# 24V-5A-buck.net
KiCad netlist of a schematic drawn in Altium Designer
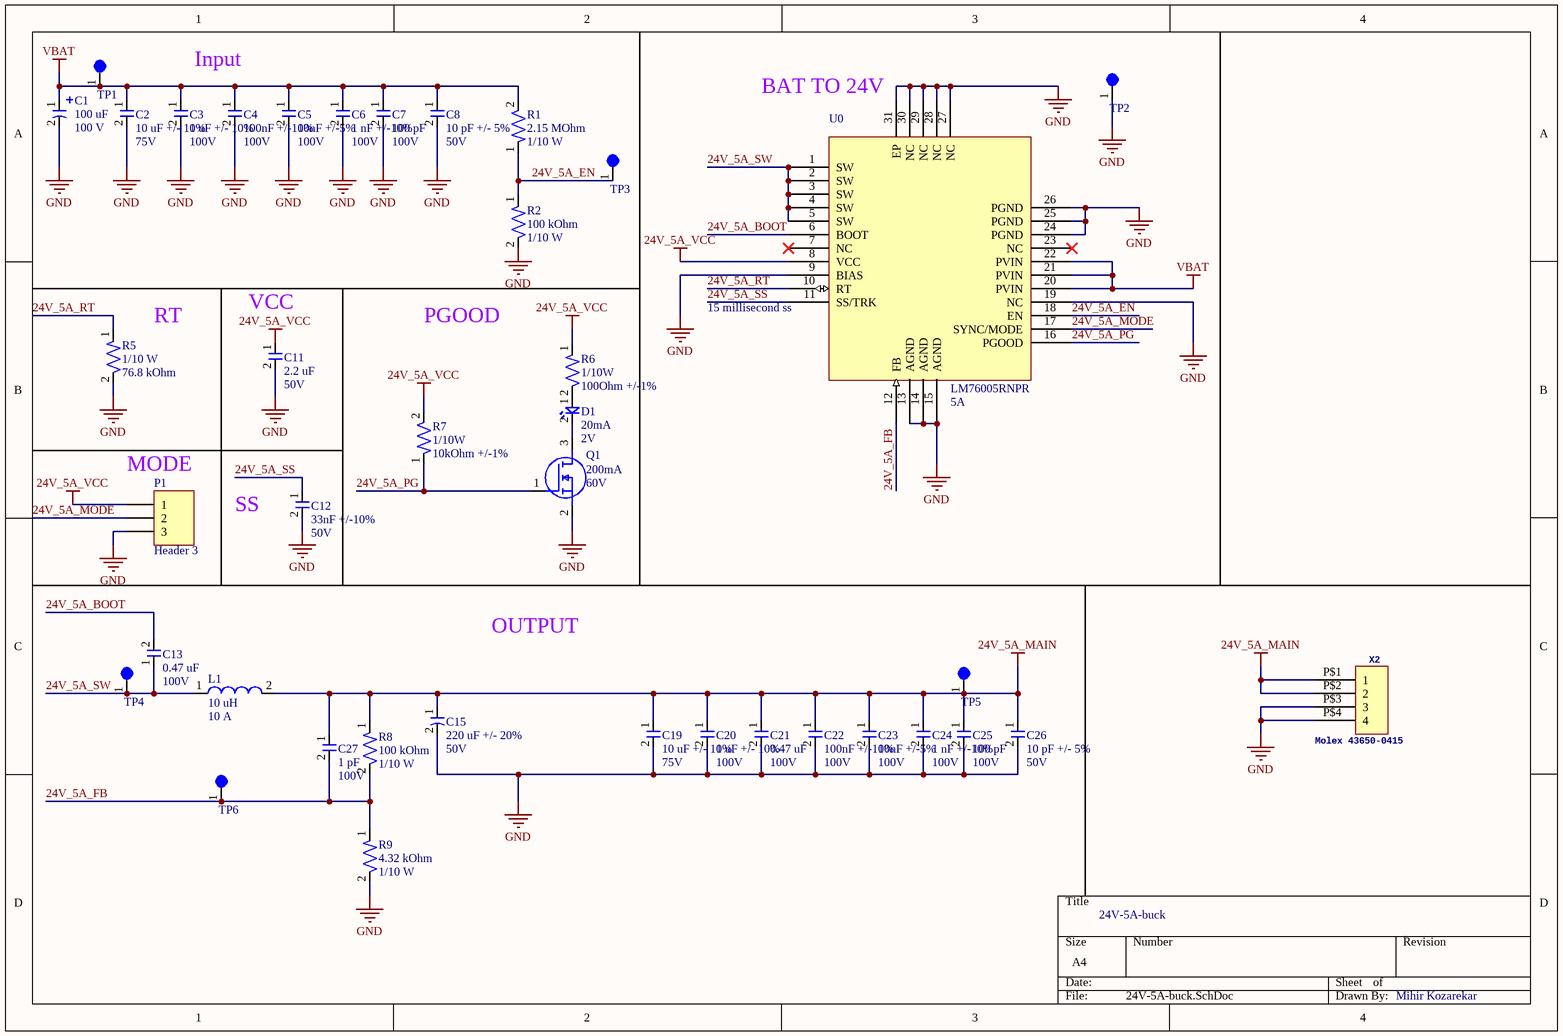
[diagram p0: 24V-5A-buck.SchDoc]

(export (version "E")
  (design (tool "Eeschema 10.0.6"))
  (components
    (comp (ref "C1")
      (value "100SEV100M12.5X16")
      (footprint "ELEC-100U-0001")
      (description "100 µF 100 V Aluminum Electrolytic Capacitors Radial, Can - SMD 2000 Hrs @ 85°C")
      (fields
        (field (name "MANUFACTURER") "Rubycon")
        (field (name "TOLERANCE") "+/- 20%")
        (field (name "CAPACITANCE") "100 uF")
        (field (name "VOLTAGE") "100 V")
      )
      (libsource (lib "MasterLib") (part "ELEC-100U-0001"))
    )
    (comp (ref "C2")
      (value "C3225X7R1N106K250AC")
      (footprint "CAP-1210")
      (description "10 µF ±10% 75V Ceramic Capacitor X7R 1210 (3225 Metric)")
      (fields (field (name "CAPACITANCE") "10 uF +/- 10%") (field (name "VOLTAGE RATING") "75V"))
      (libsource (lib "MasterLib") (part "CAP-10U-0004"))
    )
    (comp (ref "C3")
      (value "CL31B105KCHNNNE")
      (footprint "CAP-1206 - duplicate")
      (description "1 µF ±10% 100V Ceramic Capacitor X7R 1206 (3216 Metric)")
      (fields (field (name "CAPACITANCE") "1 uF +/- 10%") (field (name "VOLTAGE") "100V"))
      (libsource (lib "MasterLib") (part "CAP-1U-0001"))
    )
    (comp (ref "C4")
      (value "CC0603KRX7R0BB104")
      (footprint "CAP-0603")
      (description "CAP CER 0.1UF 100V X7R 0603")
      (fields
        (field (name "MANUFACTURER") "YAGEO")
        (field (name "CAPACITANCE") "100nF +/-10%")
        (field (name "VOLTAGE RATING") "100V")
      )
      (libsource (lib "MasterLib") (part "CAP-100N-0001"))
    )
    (comp (ref "C5")
      (value "C1608C0G2A103J080AC")
      (footprint "CAP-0603")
      (description "CAP CER 10000PF 100V C0G 0603")
      (fields
        (field (name "MANUFACTURER") "TDK Corporation")
        (field (name "CAPACITANCE") "10nF +/-5%")
        (field (name "VOLTAGE RATING") "100V")
      )
      (libsource (lib "MasterLib") (part "CAP-10N-0002"))
    )
    (comp (ref "C6")
      (value "C0603Y102K1RAC7867")
      (footprint "CAP-0603")
      (description "1000 pF ±10% 100V Ceramic Capacitor X7R 0603 (1608 Metric)")
      (fields (field (name "CAPACITANCE") "1 nF +/-10%") (field (name "VOLTAGE") "100V"))
      (libsource (lib "MasterLib") (part "CAP-1N-0001"))
    )
    (comp (ref "C7")
      (value "0603N101J101CT")
      (footprint "CAP-0603")
      (description "100 pF ±5% 100V Ceramic Capacitor C0G, NP0 0603 (1608 Metric)")
      (fields
        (field (name "TOLERANCE") "+/-5%")
        (field (name "CAPACITANCE") "100 pF")
        (field (name "VOLTAGE") "100V")
      )
      (libsource (lib "MasterLib") (part "CAP-100P-0002"))
    )
    (comp (ref "C8")
      (value "0603N100J500CT")
      (footprint "CAP-0603")
      (description "10 pF ±5% 50V Ceramic Capacitor C0G, NP0 0603 (1608 Metric)")
      (fields
        (field (name "MANUFACTURER") "Walshin Technology Corporation")
        (field (name "CAPACITANCE") "10 pF +/- 5%")
        (field (name "VOLTAGE RATING") "50V")
      )
      (libsource (lib "MasterLib") (part "CAP-10P-0001"))
    )
    (comp (ref "C11")
      (value "UMK107BBJ225KA-T")
      (footprint "CAP-0603")
      (description "2.2 µF ±10% 50V Ceramic Capacitor X5R 0603 (1608 Metric)")
      (fields (field (name "CAPACITANCE") "2.2 uF") (field (name "OLTAGE") "50V"))
      (libsource (lib "MasterLib") (part "CAP-2.2U-0001"))
    )
    (comp (ref "C12")
      (value "CC0603KRX7R9BB333")
      (footprint "CAP-0603")
      (description "0.033 µF ±10% 50V Ceramic Capacitor X7R 0603 (1608 Metric)")
      (fields
        (field (name "MANUFACTURER") "YAGEO")
        (field (name "CAPACITANCE") "33nF +/-10%")
        (field (name "VOLTAGE RATING") "50V")
      )
      (libsource (lib "MasterLib") (part "CAP-33N-0001"))
    )
    (comp (ref "C13")
      (value "KAM21KR72A474KL")
      (footprint "CAP-0805")
      (description "0.47 µF ±10% 100V Ceramic Capacitor X7R 0805 (2012 Metric)")
      (fields
        (field (name "TOLERANCE") "+/- 10%")
        (field (name "CAPACITANCE") "0.47 uF")
        (field (name "VOLTAGE") "100V")
      )
      (libsource (lib "MasterLib") (part "CAP-0.47U-0001"))
    )
    (comp (ref "C15")
      (value "50TZV220M10X10.5")
      (footprint "ELEC-220U-0003")
      (description "220 µF 50 V Aluminum Electrolytic Capacitors Radial, Can - SMD 2000 Hrs @ 105°C")
      (fields (field (name "CAPACITANCE") "220 uF +/- 20%") (field (name "VOLTAGE RATING") "50V"))
      (libsource (lib "MasterLib") (part "ELEC-220U-0003"))
    )
    (comp (ref "C19")
      (value "C3225X7R1N106K250AC")
      (footprint "CAP-1210")
      (description "10 µF ±10% 75V Ceramic Capacitor X7R 1210 (3225 Metric)")
      (fields (field (name "CAPACITANCE") "10 uF +/- 10%") (field (name "VOLTAGE RATING") "75V"))
      (libsource (lib "MasterLib") (part "CAP-10U-0004"))
    )
    (comp (ref "C20")
      (value "CL31B105KCHNNNE")
      (footprint "CAP-1206 - duplicate")
      (description "1 µF ±10% 100V Ceramic Capacitor X7R 1206 (3216 Metric)")
      (fields (field (name "CAPACITANCE") "1 uF +/- 10%") (field (name "VOLTAGE") "100V"))
      (libsource (lib "MasterLib") (part "CAP-1U-0001"))
    )
    (comp (ref "C21")
      (value "KAM21KR72A474KL")
      (footprint "CAP-0805")
      (description "0.47 µF ±10% 100V Ceramic Capacitor X7R 0805 (2012 Metric)")
      (fields
        (field (name "TOLERANCE") "+/- 10%")
        (field (name "CAPACITANCE") "0.47 uF")
        (field (name "VOLTAGE") "100V")
      )
      (libsource (lib "MasterLib") (part "CAP-0.47U-0001"))
    )
    (comp (ref "C22")
      (value "CC0603KRX7R0BB104")
      (footprint "CAP-0603")
      (description "CAP CER 0.1UF 100V X7R 0603")
      (fields
        (field (name "MANUFACTURER") "YAGEO")
        (field (name "CAPACITANCE") "100nF +/-10%")
        (field (name "VOLTAGE RATING") "100V")
      )
      (libsource (lib "MasterLib") (part "CAP-100N-0001"))
    )
    (comp (ref "C23")
      (value "C1608C0G2A103J080AC")
      (footprint "CAP-0603")
      (description "CAP CER 10000PF 100V C0G 0603")
      (fields
        (field (name "MANUFACTURER") "TDK Corporation")
        (field (name "CAPACITANCE") "10nF +/-5%")
        (field (name "VOLTAGE RATING") "100V")
      )
      (libsource (lib "MasterLib") (part "CAP-10N-0002"))
    )
    (comp (ref "C24")
      (value "C0603Y102K1RAC7867")
      (footprint "CAP-0603")
      (description "1000 pF ±10% 100V Ceramic Capacitor X7R 0603 (1608 Metric)")
      (fields (field (name "CAPACITANCE") "1 nF +/-10%") (field (name "VOLTAGE") "100V"))
      (libsource (lib "MasterLib") (part "CAP-1N-0001"))
    )
    (comp (ref "C25")
      (value "0603N101J101CT")
      (footprint "CAP-0603")
      (description "100 pF ±5% 100V Ceramic Capacitor C0G, NP0 0603 (1608 Metric)")
      (fields
        (field (name "TOLERANCE") "+/-5%")
        (field (name "CAPACITANCE") "100 pF")
        (field (name "VOLTAGE") "100V")
      )
      (libsource (lib "MasterLib") (part "CAP-100P-0002"))
    )
    (comp (ref "C26")
      (value "0603N100J500CT")
      (footprint "CAP-0603")
      (description "10 pF ±5% 50V Ceramic Capacitor C0G, NP0 0603 (1608 Metric)")
      (fields
        (field (name "MANUFACTURER") "Walshin Technology Corporation")
        (field (name "CAPACITANCE") "10 pF +/- 5%")
        (field (name "VOLTAGE RATING") "50V")
      )
      (libsource (lib "MasterLib") (part "CAP-10P-0001"))
    )
    (comp (ref "C27")
      (value "885012006087")
      (footprint "CAP-0603")
      (description "1 pF ±0.25pF 100V Ceramic Capacitor C0G, NP0 0603 (1608 Metric)")
      (fields
        (field (name "TOLERANCE") "+/- 0.25 pF")
        (field (name "CAPACITANCE") "1 pF")
        (field (name "VOLTAGE") "100V")
      )
      (libsource (lib "MasterLib") (part "CAP-1P-0001"))
    )
    (comp (ref "D1")
      (value "150060AS75000")
      (footprint "LED-0603")
      (description "CAP CER 0.1UF 100V X7R 0603")
      (fields
        (field (name "MANUFACTURER") "Wurth Electronik")
        (field (name "CURRENT RATING") "20mA")
        (field (name "VF") "2V")
      )
      (libsource (lib "MasterLib") (part "LED_Amber_0001"))
    )
    (comp (ref "L1")
      (value "SRP1270-100M")
      (footprint "PWRIND-10U-0002")
      (description "10 µH Shielded Drum Core, Wirewound Inductor 10 A 16.8mOhm Max Nonstandard")
      (fields
        (field (name "TOLERANCE") "+/- 20%")
        (field (name "INDUCTANCE") "10 uH")
        (field (name "DCI") "10 A")
      )
      (libsource (lib "MasterLib") (part "PWRIND-10U-0002"))
    )
    (comp (ref "P1")
      (value "Header 3")
      (footprint "HDR1X3")
      (description "Header, 3-Pin")
      (fields (field (name "PUBLISHER") "Altium Limited"))
      (libsource (lib "Miscellaneous Connectors") (part "Header 3"))
    )
    (comp (ref "Q1")
      (value "T2N7002AK,LM")
      (footprint "NMOS-SOT23-3")
      (description "MOSFET N-CH 60V 200MA SOT23")
      (fields
        (field (name "MANUFACTURER") "Toshiba")
        (field (name "ID-CONTINUOUS") "200mA")
        (field (name "VDS-MAX") "60V")
      )
      (libsource (lib "MasterLib") (part "NMOS-200MA-0001"))
    )
    (comp (ref "R1")
      (value "RC0603FR-072M15L")
      (footprint "RES-0603")
      (description "2.15 MOhms ±1% 0.1W, 1/10W Chip Resistor 0603 (1608 Metric) Moisture Resistant Thick Film")
      (fields
        (field (name "TOLERANCE") "+/-1%")
        (field (name "RESISTANCE") "2.15 MOhm")
        (field (name "POWER") "1/10 W")
      )
      (libsource (lib "MasterLib") (part "RES-2.15M-0001"))
    )
    (comp (ref "R2")
      (value "RC0603FR-07100KL")
      (footprint "RES-0603")
      (description "100 kOhms ±1% 0.1W, 1/10W Chip Resistor 0603 (1608 Metric) Moisture Resistant Thick Film")
      (fields
        (field (name "TOLERANCE") "+/- 1%")
        (field (name "RESISTANCE") "100 kOhm")
        (field (name "POWER") "1/10 W")
      )
      (libsource (lib "MasterLib") (part "RES-100K-0003"))
    )
    (comp (ref "R5")
      (value "RC0603FR-0776K8L")
      (footprint "RES-0603")
      (description "76.8 kOhms ±1% 0.1W, 1/10W Chip Resistor 0603 (1608 Metric) Moisture Resistant Thick Film")
      (fields
        (field (name "MANUFACTURER") "Yageo")
        (field (name "TOLERANCE") "+/- 1%")
        (field (name "POWER") "1/10 W")
        (field (name "RESISTANCE") "76.8 kOhm")
      )
      (libsource (lib "MasterLib") (part "RES-76.8K-0001"))
    )
    (comp (ref "R6")
      (value "AC0603FR-10100RL")
      (footprint "RES-0603")
      (description "100 Ohms ±1% 0.1W, 1/10W Chip Resistor 0603 (1608 Metric) Automotive AEC-Q200 Thick Film")
      (fields
        (field (name "MANUFACTURER") "YAGEO")
        (field (name "POWER RATING") "1/10W")
        (field (name "RESISTANCE") "100Ohm +/-1%")
      )
      (libsource (lib "MasterLib") (part "RES-100-0002"))
    )
    (comp (ref "R7")
      (value "RC0603FR-0710KP")
      (footprint "RES-0603")
      (description "RES SMD 10K OHM 1% 1/10W 0603")
      (fields
        (field (name "MANUFACTURER") "YAGEO")
        (field (name "POWER RATING") "1/10W")
        (field (name "RESISTANCE") "10kOhm +/-1%")
      )
      (libsource (lib "MasterLib") (part "RES-10K-0002"))
    )
    (comp (ref "R8")
      (value "RC0603FR-07100KL")
      (footprint "RES-0603")
      (description "100 kOhms ±1% 0.1W, 1/10W Chip Resistor 0603 (1608 Metric) Moisture Resistant Thick Film")
      (fields
        (field (name "TOLERANCE") "+/- 1%")
        (field (name "RESISTANCE") "100 kOhm")
        (field (name "POWER") "1/10 W")
      )
      (libsource (lib "MasterLib") (part "RES-100K-0003"))
    )
    (comp (ref "R9")
      (value "RC0603FR-074K32L")
      (footprint "RES-0603")
      (description "4.32 kOhms ±1% 0.1W, 1/10W Chip Resistor 0603 (1608 Metric) Moisture Resistant Thick Film")
      (fields
        (field (name "TOLERANCE") "+/-1%")
        (field (name "RESISTANCE") "4.32 kOhm")
        (field (name "POWER") "1/10 W")
      )
      (libsource (lib "MasterLib") (part "RES-4.32K-0001"))
    )
    (comp (ref "TP1")
      (value "5003")
      (footprint "TEST-POINT-0001")
      (description "Oranange PC Test Point, Miniature Phoisphor Bronze Silver Plating Through Hole Mounting Type")
      (libsource (lib "MasterLib") (part "TEST-POINT-0001"))
    )
    (comp (ref "TP2")
      (value "5003")
      (footprint "TEST-POINT-0001")
      (description "Oranange PC Test Point, Miniature Phoisphor Bronze Silver Plating Through Hole Mounting Type")
      (libsource (lib "MasterLib") (part "TEST-POINT-0001"))
    )
    (comp (ref "TP3")
      (value "5003")
      (footprint "TEST-POINT-0001")
      (description "Oranange PC Test Point, Miniature Phoisphor Bronze Silver Plating Through Hole Mounting Type")
      (libsource (lib "MasterLib") (part "TEST-POINT-0001"))
    )
    (comp (ref "TP4")
      (value "5003")
      (footprint "TEST-POINT-0001")
      (description "Oranange PC Test Point, Miniature Phoisphor Bronze Silver Plating Through Hole Mounting Type")
      (libsource (lib "MasterLib") (part "TEST-POINT-0001"))
    )
    (comp (ref "TP5")
      (value "5003")
      (footprint "TEST-POINT-0001")
      (description "Oranange PC Test Point, Miniature Phoisphor Bronze Silver Plating Through Hole Mounting Type")
      (libsource (lib "MasterLib") (part "TEST-POINT-0001"))
    )
    (comp (ref "TP6")
      (value "5003")
      (footprint "TEST-POINT-0001")
      (description "Oranange PC Test Point, Miniature Phoisphor Bronze Silver Plating Through Hole Mounting Type")
      (libsource (lib "MasterLib") (part "TEST-POINT-0001"))
    )
    (comp (ref "U0")
      (value "LM76005RNPR")
      (footprint "IC-30-WQFN(6x4)")
      (description "Buck Switching Regulator IC Positive Adjustable 1V 1 Output 5A 30-WFQFN Exposed Pad")
      (fields (field (name "MANUFACTURER") "Texas Instruments") (field (name "CURRENT") "5A"))
      (libsource (lib "MasterLib") (part "IC-BUCK-0006"))
    )
    (comp (ref "X2")
      (value "Molex 43650-0415")
      (footprint "43650-0415")
      (libsource (lib "Molex Microfit") (part "Micro-Fit Molex 4 Pin Vertical"))
    )
  )
  (nets
    (net (code "1") (name "/24V_5A_BOOT") (class "Default")
      (node (ref "C13") (pin "2") (pinfunction "2_2") (pintype "passive"))
      (node (ref "U0") (pin "6") (pinfunction "BOOT_6") (pintype "power_in"))
    )
    (net (code "2") (name "/24V_5A_EN") (class "Default")
      (node (ref "R1") (pin "1") (pinfunction "1_1") (pintype "passive"))
      (node (ref "R2") (pin "1") (pinfunction "1_1") (pintype "passive"))
      (node (ref "TP3") (pin "1") (pinfunction "0_1") (pintype "passive"))
      (node (ref "U0") (pin "18") (pinfunction "EN_18") (pintype "power_in"))
    )
    (net (code "3") (name "/24V_5A_FB") (class "Default")
      (node (ref "C27") (pin "2") (pinfunction "2_2") (pintype "passive"))
      (node (ref "R8") (pin "2") (pinfunction "2_2") (pintype "passive"))
      (node (ref "R9") (pin "1") (pinfunction "1_1") (pintype "passive"))
      (node (ref "TP6") (pin "1") (pinfunction "0_1") (pintype "passive"))
      (node (ref "U0") (pin "12") (pinfunction "FB_12") (pintype "input"))
    )
    (net (code "4") (name "/24V_5A_MODE") (class "Default")
      (node (ref "P1") (pin "2") (pinfunction "2_2") (pintype "passive"))
      (node (ref "U0") (pin "17") (pinfunction "SYNC/MODE_17") (pintype "power_in"))
    )
    (net (code "5") (name "/24V_5A_PG") (class "Default")
      (node (ref "Q1") (pin "1") (pinfunction "G_1") (pintype "passive"))
      (node (ref "R7") (pin "1") (pinfunction "1_1") (pintype "passive"))
      (node (ref "U0") (pin "16") (pinfunction "PGOOD_16") (pintype "power_in"))
    )
    (net (code "6") (name "/24V_5A_RT") (class "Default")
      (node (ref "R5") (pin "1") (pinfunction "1_1") (pintype "passive"))
      (node (ref "U0") (pin "10") (pinfunction "RT_10") (pintype "bidirectional"))
    )
    (net (code "7") (name "/24V_5A_SS") (class "Default")
      (node (ref "C12") (pin "1") (pinfunction "1_1") (pintype "passive"))
      (node (ref "U0") (pin "11") (pinfunction "SS/TRK_11") (pintype "passive"))
    )
    (net (code "8") (name "/24V_5A_SW") (class "Default")
      (node (ref "C13") (pin "1") (pinfunction "1_1") (pintype "passive"))
      (node (ref "L1") (pin "1") (pinfunction "1_1") (pintype "passive"))
      (node (ref "TP4") (pin "1") (pinfunction "0_1") (pintype "passive"))
      (node (ref "U0") (pin "1") (pinfunction "SW_1") (pintype "power_in"))
      (node (ref "U0") (pin "2") (pinfunction "SW_2") (pintype "power_in"))
      (node (ref "U0") (pin "3") (pinfunction "SW_3") (pintype "power_in"))
      (node (ref "U0") (pin "4") (pinfunction "SW_4") (pintype "power_in"))
      (node (ref "U0") (pin "5") (pinfunction "SW_5") (pintype "power_in"))
    )
    (net (code "9") (name "24V_5A_MAIN") (class "Default")
      (node (ref "C15") (pin "1") (pinfunction "1_1") (pintype "passive"))
      (node (ref "C19") (pin "1") (pinfunction "1_1") (pintype "passive"))
      (node (ref "C20") (pin "1") (pinfunction "1_1") (pintype "passive"))
      (node (ref "C21") (pin "1") (pinfunction "1_1") (pintype "passive"))
      (node (ref "C22") (pin "1") (pinfunction "1_1") (pintype "passive"))
      (node (ref "C23") (pin "1") (pinfunction "1_1") (pintype "passive"))
      (node (ref "C24") (pin "1") (pinfunction "1_1") (pintype "passive"))
      (node (ref "C25") (pin "1") (pinfunction "1_1") (pintype "passive"))
      (node (ref "C26") (pin "1") (pinfunction "1_1") (pintype "passive"))
      (node (ref "C27") (pin "1") (pinfunction "1_1") (pintype "passive"))
      (node (ref "L1") (pin "2") (pinfunction "2_2") (pintype "passive"))
      (node (ref "R8") (pin "1") (pinfunction "1_1") (pintype "passive"))
      (node (ref "TP5") (pin "1") (pinfunction "0_1") (pintype "passive"))
      (node (ref "X2") (pin "P$1") (pinfunction "1_P$1") (pintype "passive"))
      (node (ref "X2") (pin "P$2") (pinfunction "2_P$2") (pintype "passive"))
    )
    (net (code "10") (name "24V_5A_VCC") (class "Default")
      (node (ref "C11") (pin "1") (pinfunction "1_1") (pintype "passive"))
      (node (ref "P1") (pin "1") (pinfunction "1_1") (pintype "passive"))
      (node (ref "R6") (pin "1") (pinfunction "1_1") (pintype "passive"))
      (node (ref "R7") (pin "2") (pinfunction "2_2") (pintype "passive"))
      (node (ref "U0") (pin "8") (pinfunction "VCC_8") (pintype "power_in"))
    )
    (net (code "11") (name "GND") (class "Default")
      (node (ref "C1") (pin "2") (pinfunction "2_2") (pintype "passive"))
      (node (ref "C11") (pin "2") (pinfunction "2_2") (pintype "passive"))
      (node (ref "C12") (pin "2") (pinfunction "2_2") (pintype "passive"))
      (node (ref "C15") (pin "2") (pinfunction "2_2") (pintype "passive"))
      (node (ref "C19") (pin "2") (pinfunction "2_2") (pintype "passive"))
      (node (ref "C2") (pin "2") (pinfunction "2_2") (pintype "passive"))
      (node (ref "C20") (pin "2") (pinfunction "2_2") (pintype "passive"))
      (node (ref "C21") (pin "2") (pinfunction "2_2") (pintype "passive"))
      (node (ref "C22") (pin "2") (pinfunction "2_2") (pintype "passive"))
      (node (ref "C23") (pin "2") (pinfunction "2_2") (pintype "passive"))
      (node (ref "C24") (pin "2") (pinfunction "2_2") (pintype "passive"))
      (node (ref "C25") (pin "2") (pinfunction "2_2") (pintype "passive"))
      (node (ref "C26") (pin "2") (pinfunction "2_2") (pintype "passive"))
      (node (ref "C3") (pin "2") (pinfunction "2_2") (pintype "passive"))
      (node (ref "C4") (pin "2") (pinfunction "2_2") (pintype "passive"))
      (node (ref "C5") (pin "2") (pinfunction "2_2") (pintype "passive"))
      (node (ref "C6") (pin "2") (pinfunction "2_2") (pintype "passive"))
      (node (ref "C7") (pin "2") (pinfunction "2_2") (pintype "passive"))
      (node (ref "C8") (pin "2") (pinfunction "2_2") (pintype "passive"))
      (node (ref "P1") (pin "3") (pinfunction "3_3") (pintype "passive"))
      (node (ref "Q1") (pin "2") (pinfunction "S_2") (pintype "passive"))
      (node (ref "R2") (pin "2") (pinfunction "2_2") (pintype "passive"))
      (node (ref "R5") (pin "2") (pinfunction "2_2") (pintype "passive"))
      (node (ref "R9") (pin "2") (pinfunction "2_2") (pintype "passive"))
      (node (ref "TP2") (pin "1") (pinfunction "0_1") (pintype "passive"))
      (node (ref "U0") (pin "13") (pinfunction "AGND_13") (pintype "power_in"))
      (node (ref "U0") (pin "14") (pinfunction "AGND_14") (pintype "power_in"))
      (node (ref "U0") (pin "15") (pinfunction "AGND_15") (pintype "power_in"))
      (node (ref "U0") (pin "19") (pinfunction "NC_19") (pintype "power_in"))
      (node (ref "U0") (pin "24") (pinfunction "PGND_24") (pintype "power_in"))
      (node (ref "U0") (pin "25") (pinfunction "PGND_25") (pintype "power_in"))
      (node (ref "U0") (pin "26") (pinfunction "PGND_26") (pintype "power_in"))
      (node (ref "U0") (pin "27") (pinfunction "NC_27") (pintype "power_in"))
      (node (ref "U0") (pin "28") (pinfunction "NC_28") (pintype "power_in"))
      (node (ref "U0") (pin "29") (pinfunction "NC_29") (pintype "power_in"))
      (node (ref "U0") (pin "30") (pinfunction "NC_30") (pintype "power_in"))
      (node (ref "U0") (pin "31") (pinfunction "EP_31") (pintype "power_in"))
      (node (ref "U0") (pin "9") (pinfunction "BIAS_9") (pintype "power_in"))
      (node (ref "X2") (pin "P$3") (pinfunction "3_P$3") (pintype "passive"))
      (node (ref "X2") (pin "P$4") (pinfunction "4_P$4") (pintype "passive"))
    )
    (net (code "12") (name "Net-(D1-Pad1)") (class "Default")
      (node (ref "D1") (pin "1") (pinfunction "1_1") (pintype "passive"))
      (node (ref "R6") (pin "2") (pinfunction "2_2") (pintype "passive"))
    )
    (net (code "13") (name "Net-(Q1-D)") (class "Default")
      (node (ref "D1") (pin "2") (pinfunction "2_2") (pintype "passive"))
      (node (ref "Q1") (pin "3") (pinfunction "D_3") (pintype "passive"))
    )
    (net (code "14") (name "VBAT") (class "Default")
      (node (ref "C1") (pin "1") (pinfunction "1_1") (pintype "passive"))
      (node (ref "C2") (pin "1") (pinfunction "1_1") (pintype "passive"))
      (node (ref "C3") (pin "1") (pinfunction "1_1") (pintype "passive"))
      (node (ref "C4") (pin "1") (pinfunction "1_1") (pintype "passive"))
      (node (ref "C5") (pin "1") (pinfunction "1_1") (pintype "passive"))
      (node (ref "C6") (pin "1") (pinfunction "1_1") (pintype "passive"))
      (node (ref "C7") (pin "1") (pinfunction "1_1") (pintype "passive"))
      (node (ref "C8") (pin "1") (pinfunction "1_1") (pintype "passive"))
      (node (ref "R1") (pin "2") (pinfunction "2_2") (pintype "passive"))
      (node (ref "TP1") (pin "1") (pinfunction "0_1") (pintype "passive"))
      (node (ref "U0") (pin "20") (pinfunction "PVIN_20") (pintype "power_in"))
      (node (ref "U0") (pin "21") (pinfunction "PVIN_21") (pintype "power_in"))
      (node (ref "U0") (pin "22") (pinfunction "PVIN_22") (pintype "power_in"))
    )
    (net (code "15") (name "unconnected-(U0-NC-Pad7)") (class "Default")
      (node (ref "U0") (pin "7") (pinfunction "NC_7") (pintype "power_in+no_connect"))
    )
    (net (code "16") (name "unconnected-(U0-NC-Pad23)") (class "Default")
      (node (ref "U0") (pin "23") (pinfunction "NC_23") (pintype "tri_state+no_connect"))
    )
  )
)
